# V4.net
KiCad netlist of a schematic drawn in EAGLE
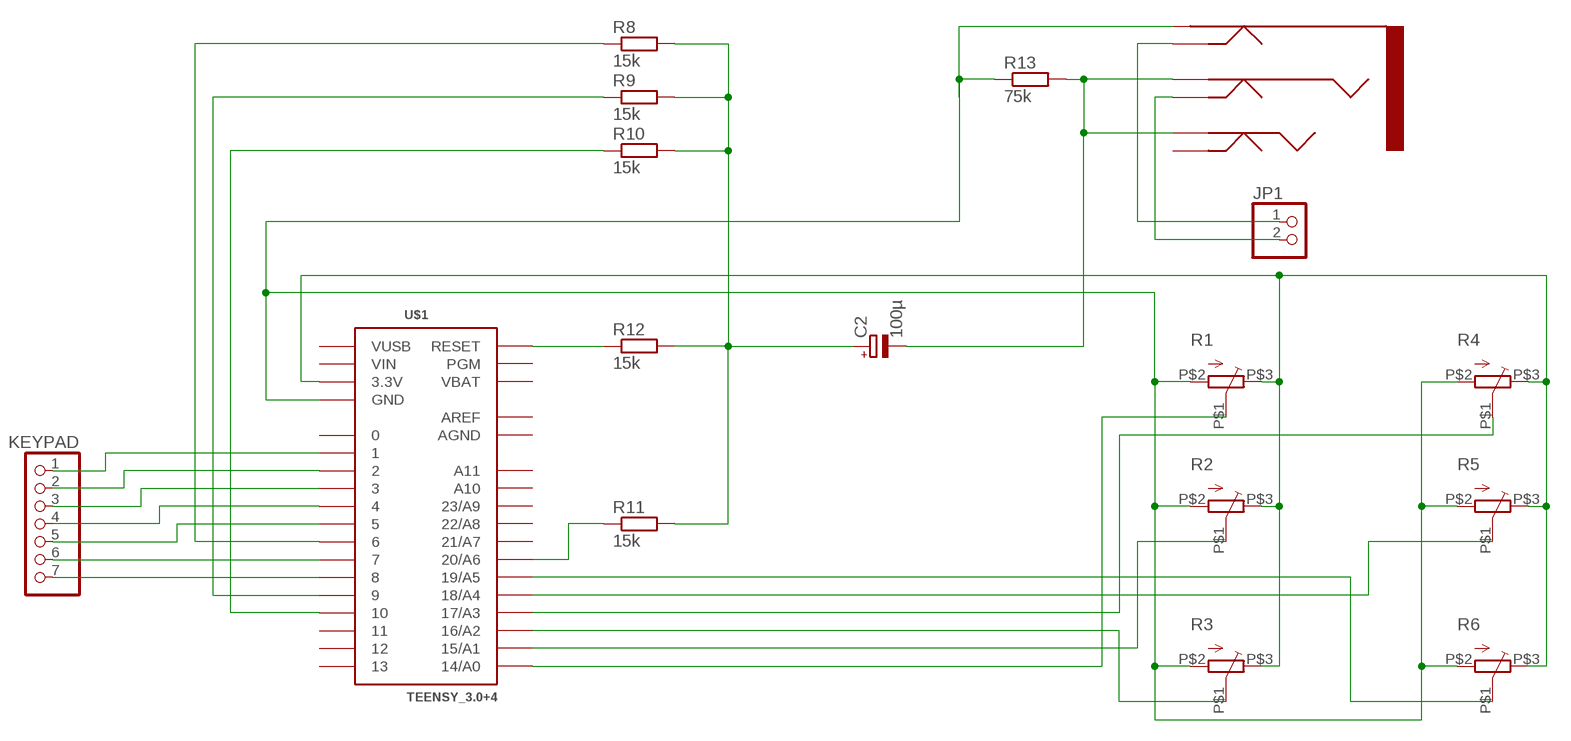
[diagram p0: schematic, sheet 1]

(export (version "E")
  (design (tool "Eeschema 10.0.6"))
  (components
    (comp (ref "C2")
      (value "100µ")
      (footprint "eagle-import:E2,5-6")
      (libsource (lib "eagle-import") (part "CPOL-EUE2.5-6"))
    )
    (comp (ref "JP1")
      (value "PINHD-1X2")
      (footprint "eagle-import:1X02")
      (libsource (lib "eagle-import") (part "PINHD-1X2"))
    )
    (comp (ref "KEYPAD")
      (value "PINHD-1X7")
      (footprint "eagle-import:1X07")
      (libsource (lib "eagle-import") (part "PINHD-1X7"))
    )
    (comp (ref "R1")
      (value "STR09K113")
      (footprint "eagle-import:STR09K113")
      (libsource (lib "eagle-import") (part "STR09K113"))
    )
    (comp (ref "R2")
      (value "STR09K113")
      (footprint "eagle-import:STR09K113")
      (libsource (lib "eagle-import") (part "STR09K113"))
    )
    (comp (ref "R3")
      (value "STR09K113")
      (footprint "eagle-import:STR09K113")
      (libsource (lib "eagle-import") (part "STR09K113"))
    )
    (comp (ref "R4")
      (value "STR09K113")
      (footprint "eagle-import:STR09K113")
      (libsource (lib "eagle-import") (part "STR09K113"))
    )
    (comp (ref "R5")
      (value "STR09K113")
      (footprint "eagle-import:STR09K113")
      (libsource (lib "eagle-import") (part "STR09K113"))
    )
    (comp (ref "R6")
      (value "STR09K113")
      (footprint "eagle-import:STR09K113")
      (libsource (lib "eagle-import") (part "STR09K113"))
    )
    (comp (ref "R8")
      (value "15k")
      (footprint "eagle-import:0309_12")
      (libsource (lib "eagle-import") (part "R-EU_0309/12"))
    )
    (comp (ref "R9")
      (value "15k")
      (footprint "eagle-import:0309_12")
      (libsource (lib "eagle-import") (part "R-EU_0309/12"))
    )
    (comp (ref "R10")
      (value "15k")
      (footprint "eagle-import:0309_12")
      (libsource (lib "eagle-import") (part "R-EU_0309/12"))
    )
    (comp (ref "R11")
      (value "15k")
      (footprint "eagle-import:0309_12")
      (libsource (lib "eagle-import") (part "R-EU_0309/12"))
    )
    (comp (ref "R12")
      (value "15k")
      (footprint "eagle-import:0309_12")
      (libsource (lib "eagle-import") (part "R-EU_0309/12"))
    )
    (comp (ref "R13")
      (value "75k")
      (footprint "eagle-import:0309_12")
      (libsource (lib "eagle-import") (part "R-EU_0309/12"))
    )
    (comp (ref "U$1")
      (value "TEENSY_3.0+4")
      (footprint "eagle-import:TEENSY_3.0+4")
      (libsource (lib "eagle-import") (part "TEENSY_3.0+4"))
    )
    (comp (ref "U$2")
      (value "CLIF_3_5")
      (footprint "eagle-import:CLIFF_3-5M")
      (libsource (lib "eagle-import") (part "CLIF_3_5"))
    )
  )
  (nets
    (net (code "1") (name "/AGND") (class "Default")
      (node (ref "U$1") (pin "AGND") (pinfunction "AGND_AGND") (pintype "power_in"))
    )
    (net (code "2") (name "/AREF") (class "Default")
      (node (ref "U$1") (pin "AREF") (pinfunction "AREF_AREF") (pintype "power_in"))
    )
    (net (code "3") (name "/VBAT") (class "Default")
      (node (ref "U$1") (pin "VBAT") (pinfunction "VBAT_VBAT") (pintype "power_in"))
    )
    (net (code "4") (name "/VIN") (class "Default")
      (node (ref "U$1") (pin "VIN") (pinfunction "VIN_VIN") (pintype "power_in"))
    )
    (net (code "5") (name "/VUSB") (class "Default")
      (node (ref "U$1") (pin "VUSB") (pinfunction "VUSB_VUSB") (pintype "power_in"))
    )
    (net (code "6") (name "Net-(C2-Pad+)") (class "Default")
      (node (ref "C2") (pin "+") (pinfunction "+_+") (pintype "passive"))
      (node (ref "R10") (pin "2") (pinfunction "2_2") (pintype "passive"))
      (node (ref "R11") (pin "2") (pinfunction "2_2") (pintype "passive"))
      (node (ref "R12") (pin "2") (pinfunction "2_2") (pintype "passive"))
      (node (ref "R8") (pin "2") (pinfunction "2_2") (pintype "passive"))
      (node (ref "R9") (pin "2") (pinfunction "2_2") (pintype "passive"))
    )
    (net (code "7") (name "Net-(C2-Pad-)") (class "Default")
      (node (ref "C2") (pin "-") (pinfunction "-_-") (pintype "passive"))
      (node (ref "R13") (pin "2") (pinfunction "2_2") (pintype "passive"))
      (node (ref "U$2") (pin "RING") (pinfunction "RING_RING") (pintype "bidirectional"))
      (node (ref "U$2") (pin "TIP") (pinfunction "TIP_TIP") (pintype "bidirectional"))
    )
    (net (code "8") (name "Net-(JP1-Pad1)") (class "Default")
      (node (ref "JP1") (pin "1") (pinfunction "1_1") (pintype "passive"))
      (node (ref "U$2") (pin "GROUND1") (pinfunction "GROUND1_GROUND1") (pintype "bidirectional"))
    )
    (net (code "9") (name "Net-(JP1-Pad2)") (class "Default")
      (node (ref "JP1") (pin "2") (pinfunction "2_2") (pintype "passive"))
      (node (ref "U$2") (pin "RING1") (pinfunction "RING1_RING1") (pintype "bidirectional"))
    )
    (net (code "10") (name "Net-(KEYPAD-Pad1)") (class "Default")
      (node (ref "KEYPAD") (pin "1") (pinfunction "1_1") (pintype "passive"))
      (node (ref "U$1") (pin "1") (pinfunction "1_1") (pintype "bidirectional"))
    )
    (net (code "11") (name "Net-(KEYPAD-Pad2)") (class "Default")
      (node (ref "KEYPAD") (pin "2") (pinfunction "2_2") (pintype "passive"))
      (node (ref "U$1") (pin "2") (pinfunction "2_2") (pintype "bidirectional"))
    )
    (net (code "12") (name "Net-(KEYPAD-Pad3)") (class "Default")
      (node (ref "KEYPAD") (pin "3") (pinfunction "3_3") (pintype "passive"))
      (node (ref "U$1") (pin "3") (pinfunction "3_3") (pintype "bidirectional"))
    )
    (net (code "13") (name "Net-(KEYPAD-Pad4)") (class "Default")
      (node (ref "KEYPAD") (pin "4") (pinfunction "4_4") (pintype "passive"))
      (node (ref "U$1") (pin "4") (pinfunction "4_4") (pintype "bidirectional"))
    )
    (net (code "14") (name "Net-(KEYPAD-Pad5)") (class "Default")
      (node (ref "KEYPAD") (pin "5") (pinfunction "5_5") (pintype "passive"))
      (node (ref "U$1") (pin "5") (pinfunction "5_5") (pintype "bidirectional"))
    )
    (net (code "15") (name "Net-(KEYPAD-Pad6)") (class "Default")
      (node (ref "KEYPAD") (pin "6") (pinfunction "6_6") (pintype "passive"))
      (node (ref "U$1") (pin "7") (pinfunction "7_7") (pintype "bidirectional"))
    )
    (net (code "16") (name "Net-(KEYPAD-Pad7)") (class "Default")
      (node (ref "KEYPAD") (pin "7") (pinfunction "7_7") (pintype "passive"))
      (node (ref "U$1") (pin "8") (pinfunction "8_8") (pintype "bidirectional"))
    )
    (net (code "17") (name "Net-(R1-E)") (class "Default")
      (node (ref "R1") (pin "P$3") (pinfunction "E_P$3") (pintype "passive"))
      (node (ref "R2") (pin "P$3") (pinfunction "E_P$3") (pintype "passive"))
      (node (ref "R3") (pin "P$3") (pinfunction "E_P$3") (pintype "passive"))
      (node (ref "R4") (pin "P$3") (pinfunction "E_P$3") (pintype "passive"))
      (node (ref "R5") (pin "P$3") (pinfunction "E_P$3") (pintype "passive"))
      (node (ref "R6") (pin "P$3") (pinfunction "E_P$3") (pintype "passive"))
      (node (ref "U$1") (pin "3.3V") (pinfunction "3.3V_3.3V") (pintype "power_in"))
      (node (ref "U$1") (pin "3.3V1") (pinfunction "3.3V_3.3V1") (pintype "power_in"))
    )
    (net (code "18") (name "Net-(R1-S)") (class "Default")
      (node (ref "R1") (pin "P$2") (pinfunction "S_P$2") (pintype "passive"))
      (node (ref "R13") (pin "1") (pinfunction "1_1") (pintype "passive"))
      (node (ref "R2") (pin "P$2") (pinfunction "S_P$2") (pintype "passive"))
      (node (ref "R3") (pin "P$2") (pinfunction "S_P$2") (pintype "passive"))
      (node (ref "R4") (pin "P$2") (pinfunction "S_P$2") (pintype "passive"))
      (node (ref "R5") (pin "P$2") (pinfunction "S_P$2") (pintype "passive"))
      (node (ref "R6") (pin "P$2") (pinfunction "S_P$2") (pintype "passive"))
      (node (ref "U$1") (pin "GND") (pinfunction "GND_GND") (pintype "power_in"))
      (node (ref "U$1") (pin "GND1") (pinfunction "GND_GND1") (pintype "power_in"))
      (node (ref "U$2") (pin "GROUND") (pinfunction "GROUND_GROUND") (pintype "bidirectional"))
    )
    (net (code "19") (name "Net-(R1-W)") (class "Default")
      (node (ref "R1") (pin "P$1") (pinfunction "W_P$1") (pintype "passive"))
      (node (ref "U$1") (pin "14/A0") (pinfunction "14/A0_14/A0") (pintype "bidirectional"))
    )
    (net (code "20") (name "Net-(R2-W)") (class "Default")
      (node (ref "R2") (pin "P$1") (pinfunction "W_P$1") (pintype "passive"))
      (node (ref "U$1") (pin "15/A1") (pinfunction "15/A1_15/A1") (pintype "bidirectional"))
    )
    (net (code "21") (name "Net-(R3-W)") (class "Default")
      (node (ref "R3") (pin "P$1") (pinfunction "W_P$1") (pintype "passive"))
      (node (ref "U$1") (pin "16/A2") (pinfunction "16/A2_16/A2") (pintype "bidirectional"))
    )
    (net (code "22") (name "Net-(R4-W)") (class "Default")
      (node (ref "R4") (pin "P$1") (pinfunction "W_P$1") (pintype "passive"))
      (node (ref "U$1") (pin "17/A3") (pinfunction "17/A3_17/A3") (pintype "bidirectional"))
    )
    (net (code "23") (name "Net-(R5-W)") (class "Default")
      (node (ref "R5") (pin "P$1") (pinfunction "W_P$1") (pintype "passive"))
      (node (ref "U$1") (pin "18/A4") (pinfunction "18/A4_18/A4") (pintype "bidirectional"))
    )
    (net (code "24") (name "Net-(R6-W)") (class "Default")
      (node (ref "R6") (pin "P$1") (pinfunction "W_P$1") (pintype "passive"))
      (node (ref "U$1") (pin "19/A5") (pinfunction "19/A5_19/A5") (pintype "bidirectional"))
    )
    (net (code "25") (name "Net-(R8-Pad1)") (class "Default")
      (node (ref "R8") (pin "1") (pinfunction "1_1") (pintype "passive"))
      (node (ref "U$1") (pin "6") (pinfunction "6_6") (pintype "bidirectional"))
    )
    (net (code "26") (name "Net-(R9-Pad1)") (class "Default")
      (node (ref "R9") (pin "1") (pinfunction "1_1") (pintype "passive"))
      (node (ref "U$1") (pin "9") (pinfunction "9_9") (pintype "bidirectional"))
    )
    (net (code "27") (name "Net-(R10-Pad1)") (class "Default")
      (node (ref "R10") (pin "1") (pinfunction "1_1") (pintype "passive"))
      (node (ref "U$1") (pin "10") (pinfunction "10_10") (pintype "bidirectional"))
    )
    (net (code "28") (name "Net-(R11-Pad1)") (class "Default")
      (node (ref "R11") (pin "1") (pinfunction "1_1") (pintype "passive"))
      (node (ref "U$1") (pin "20/A6") (pinfunction "20/A6_20/A6") (pintype "bidirectional"))
    )
    (net (code "29") (name "Net-(R12-Pad1)") (class "Default")
      (node (ref "R12") (pin "1") (pinfunction "1_1") (pintype "passive"))
      (node (ref "U$1") (pin "RESET") (pinfunction "RESET_RESET") (pintype "bidirectional"))
    )
    (net (code "30") (name "unconnected-(U$1-Pad0)") (class "Default")
      (node (ref "U$1") (pin "0") (pinfunction "0_0") (pintype "bidirectional"))
    )
    (net (code "31") (name "unconnected-(U$1-Pad11)") (class "Default")
      (node (ref "U$1") (pin "11") (pinfunction "11_11") (pintype "bidirectional"))
    )
    (net (code "32") (name "unconnected-(U$1-Pad12)") (class "Default")
      (node (ref "U$1") (pin "12") (pinfunction "12_12") (pintype "bidirectional"))
    )
    (net (code "33") (name "unconnected-(U$1-Pad13)") (class "Default")
      (node (ref "U$1") (pin "13") (pinfunction "13_13") (pintype "bidirectional"))
    )
    (net (code "34") (name "unconnected-(U$1-Pad21{slash}A7)") (class "Default")
      (node (ref "U$1") (pin "21/A7") (pinfunction "21/A7_21/A7") (pintype "bidirectional"))
    )
    (net (code "35") (name "unconnected-(U$1-Pad22{slash}A8)") (class "Default")
      (node (ref "U$1") (pin "22/A8") (pinfunction "22/A8_22/A8") (pintype "bidirectional"))
    )
    (net (code "36") (name "unconnected-(U$1-Pad23{slash}A9)") (class "Default")
      (node (ref "U$1") (pin "23/A9") (pinfunction "23/A9_23/A9") (pintype "bidirectional"))
    )
    (net (code "37") (name "unconnected-(U$1-PadA10)") (class "Default")
      (node (ref "U$1") (pin "A10") (pinfunction "A10_A10") (pintype "bidirectional"))
    )
    (net (code "38") (name "unconnected-(U$1-PadA11)") (class "Default")
      (node (ref "U$1") (pin "A11") (pinfunction "A11_A11") (pintype "bidirectional"))
    )
    (net (code "39") (name "unconnected-(U$1-PadPGM)") (class "Default")
      (node (ref "U$1") (pin "PGM") (pinfunction "PGM_PGM") (pintype "bidirectional"))
    )
    (net (code "40") (name "unconnected-(U$2-PadTIP1)") (class "Default")
      (node (ref "U$2") (pin "TIP1") (pinfunction "TIP1_TIP1") (pintype "bidirectional"))
    )
  )
)
